# FPGA_Banks_DDR3.net
KiCad netlist of a schematic drawn in Altium Designer
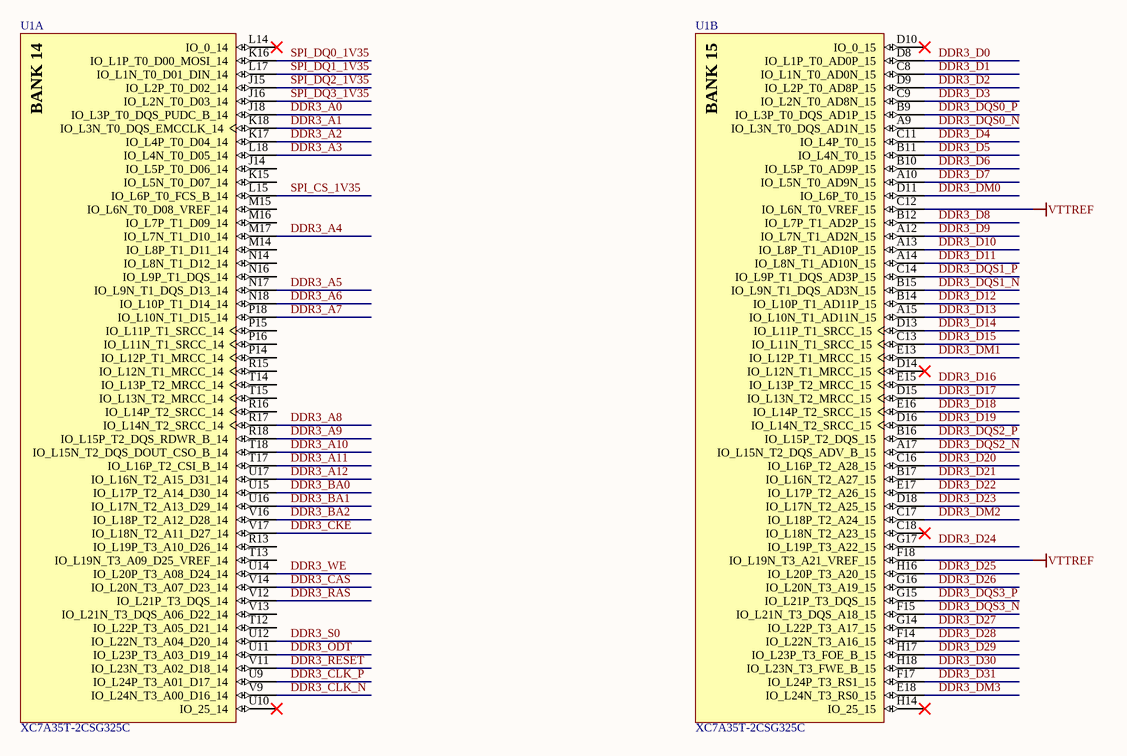
[diagram p0: FPGA_Banks_DDR3.SchDoc]

(export (version "E")
  (design (tool "Eeschema 10.0.6"))
  (components
    (comp (ref "U1")
      (value "XC7A35T-2CSG325C")
      (footprint "CSG325")
      (description "Artix-7 FPGA, 150 User I/Os, 4 GTP, 324-Ball BGA, Speed Grade 2, Commercial Grade, Pb-Free")
      (fields (field (name "MANUFACTURER") "Xilinx"))
      (libsource (lib "Xilinx Artix-7") (part "XC7A35T-2CSG325C"))
    )
  )
  (nets
    (net (code "1") (name "/DDR3_A0") (class "Default")
      (node (ref "U1") (pin "J18") (pinfunction "IO_L3P_T0_DQS_PUDC_B_14_J18") (pintype "bidirectional"))
    )
    (net (code "2") (name "/DDR3_A1") (class "Default")
      (node (ref "U1") (pin "K18") (pinfunction "IO_L3N_T0_DQS_EMCCLK_14_K18") (pintype "bidirectional"))
    )
    (net (code "3") (name "/DDR3_A2") (class "Default")
      (node (ref "U1") (pin "K17") (pinfunction "IO_L4P_T0_D04_14_K17") (pintype "bidirectional"))
    )
    (net (code "4") (name "/DDR3_A3") (class "Default")
      (node (ref "U1") (pin "L18") (pinfunction "IO_L4N_T0_D05_14_L18") (pintype "bidirectional"))
    )
    (net (code "5") (name "/DDR3_A4") (class "Default")
      (node (ref "U1") (pin "M17") (pinfunction "IO_L7N_T1_D10_14_M17") (pintype "bidirectional"))
    )
    (net (code "6") (name "/DDR3_A5") (class "Default")
      (node (ref "U1") (pin "N17") (pinfunction "IO_L9N_T1_DQS_D13_14_N17") (pintype "bidirectional"))
    )
    (net (code "7") (name "/DDR3_A6") (class "Default")
      (node (ref "U1") (pin "N18") (pinfunction "IO_L10P_T1_D14_14_N18") (pintype "bidirectional"))
    )
    (net (code "8") (name "/DDR3_A7") (class "Default")
      (node (ref "U1") (pin "P18") (pinfunction "IO_L10N_T1_D15_14_P18") (pintype "bidirectional"))
    )
    (net (code "9") (name "/DDR3_A8") (class "Default")
      (node (ref "U1") (pin "R17") (pinfunction "IO_L14N_T2_SRCC_14_R17") (pintype "bidirectional"))
    )
    (net (code "10") (name "/DDR3_A9") (class "Default")
      (node (ref "U1") (pin "R18") (pinfunction "IO_L15P_T2_DQS_RDWR_B_14_R18") (pintype "bidirectional"))
    )
    (net (code "11") (name "/DDR3_A10") (class "Default")
      (node (ref "U1") (pin "T18") (pinfunction "IO_L15N_T2_DQS_DOUT_CSO_B_14_T18") (pintype "bidirectional"))
    )
    (net (code "12") (name "/DDR3_A11") (class "Default")
      (node (ref "U1") (pin "T17") (pinfunction "IO_L16P_T2_CSI_B_14_T17") (pintype "bidirectional"))
    )
    (net (code "13") (name "/DDR3_A12") (class "Default")
      (node (ref "U1") (pin "U17") (pinfunction "IO_L16N_T2_A15_D31_14_U17") (pintype "bidirectional"))
    )
    (net (code "14") (name "/DDR3_BA0") (class "Default")
      (node (ref "U1") (pin "U15") (pinfunction "IO_L17P_T2_A14_D30_14_U15") (pintype "bidirectional"))
    )
    (net (code "15") (name "/DDR3_BA1") (class "Default")
      (node (ref "U1") (pin "U16") (pinfunction "IO_L17N_T2_A13_D29_14_U16") (pintype "bidirectional"))
    )
    (net (code "16") (name "/DDR3_BA2") (class "Default")
      (node (ref "U1") (pin "V16") (pinfunction "IO_L18P_T2_A12_D28_14_V16") (pintype "bidirectional"))
    )
    (net (code "17") (name "/DDR3_CAS") (class "Default")
      (node (ref "U1") (pin "V14") (pinfunction "IO_L20N_T3_A07_D23_14_V14") (pintype "bidirectional"))
    )
    (net (code "18") (name "/DDR3_CKE") (class "Default")
      (node (ref "U1") (pin "V17") (pinfunction "IO_L18N_T2_A11_D27_14_V17") (pintype "bidirectional"))
    )
    (net (code "19") (name "/DDR3_CLK_N") (class "Default")
      (node (ref "U1") (pin "V9") (pinfunction "IO_L24N_T3_A00_D16_14_V9") (pintype "bidirectional"))
    )
    (net (code "20") (name "/DDR3_CLK_P") (class "Default")
      (node (ref "U1") (pin "U9") (pinfunction "IO_L24P_T3_A01_D17_14_U9") (pintype "bidirectional"))
    )
    (net (code "21") (name "/DDR3_D0") (class "Default")
      (node (ref "U1") (pin "D8") (pinfunction "IO_L1P_T0_AD0P_15_D8") (pintype "bidirectional"))
    )
    (net (code "22") (name "/DDR3_D1") (class "Default")
      (node (ref "U1") (pin "C8") (pinfunction "IO_L1N_T0_AD0N_15_C8") (pintype "bidirectional"))
    )
    (net (code "23") (name "/DDR3_D2") (class "Default")
      (node (ref "U1") (pin "D9") (pinfunction "IO_L2P_T0_AD8P_15_D9") (pintype "bidirectional"))
    )
    (net (code "24") (name "/DDR3_D3") (class "Default")
      (node (ref "U1") (pin "C9") (pinfunction "IO_L2N_T0_AD8N_15_C9") (pintype "bidirectional"))
    )
    (net (code "25") (name "/DDR3_D4") (class "Default")
      (node (ref "U1") (pin "C11") (pinfunction "IO_L4P_T0_15_C11") (pintype "bidirectional"))
    )
    (net (code "26") (name "/DDR3_D5") (class "Default")
      (node (ref "U1") (pin "B11") (pinfunction "IO_L4N_T0_15_B11") (pintype "bidirectional"))
    )
    (net (code "27") (name "/DDR3_D6") (class "Default")
      (node (ref "U1") (pin "B10") (pinfunction "IO_L5P_T0_AD9P_15_B10") (pintype "bidirectional"))
    )
    (net (code "28") (name "/DDR3_D7") (class "Default")
      (node (ref "U1") (pin "A10") (pinfunction "IO_L5N_T0_AD9N_15_A10") (pintype "bidirectional"))
    )
    (net (code "29") (name "/DDR3_D8") (class "Default")
      (node (ref "U1") (pin "B12") (pinfunction "IO_L7P_T1_AD2P_15_B12") (pintype "bidirectional"))
    )
    (net (code "30") (name "/DDR3_D9") (class "Default")
      (node (ref "U1") (pin "A12") (pinfunction "IO_L7N_T1_AD2N_15_A12") (pintype "bidirectional"))
    )
    (net (code "31") (name "/DDR3_D10") (class "Default")
      (node (ref "U1") (pin "A13") (pinfunction "IO_L8P_T1_AD10P_15_A13") (pintype "bidirectional"))
    )
    (net (code "32") (name "/DDR3_D11") (class "Default")
      (node (ref "U1") (pin "A14") (pinfunction "IO_L8N_T1_AD10N_15_A14") (pintype "bidirectional"))
    )
    (net (code "33") (name "/DDR3_D12") (class "Default")
      (node (ref "U1") (pin "B14") (pinfunction "IO_L10P_T1_AD11P_15_B14") (pintype "bidirectional"))
    )
    (net (code "34") (name "/DDR3_D13") (class "Default")
      (node (ref "U1") (pin "A15") (pinfunction "IO_L10N_T1_AD11N_15_A15") (pintype "bidirectional"))
    )
    (net (code "35") (name "/DDR3_D14") (class "Default")
      (node (ref "U1") (pin "D13") (pinfunction "IO_L11P_T1_SRCC_15_D13") (pintype "bidirectional"))
    )
    (net (code "36") (name "/DDR3_D15") (class "Default")
      (node (ref "U1") (pin "C13") (pinfunction "IO_L11N_T1_SRCC_15_C13") (pintype "bidirectional"))
    )
    (net (code "37") (name "/DDR3_D16") (class "Default")
      (node (ref "U1") (pin "E15") (pinfunction "IO_L13P_T2_MRCC_15_E15") (pintype "bidirectional"))
    )
    (net (code "38") (name "/DDR3_D17") (class "Default")
      (node (ref "U1") (pin "D15") (pinfunction "IO_L13N_T2_MRCC_15_D15") (pintype "bidirectional"))
    )
    (net (code "39") (name "/DDR3_D18") (class "Default")
      (node (ref "U1") (pin "E16") (pinfunction "IO_L14P_T2_SRCC_15_E16") (pintype "bidirectional"))
    )
    (net (code "40") (name "/DDR3_D19") (class "Default")
      (node (ref "U1") (pin "D16") (pinfunction "IO_L14N_T2_SRCC_15_D16") (pintype "bidirectional"))
    )
    (net (code "41") (name "/DDR3_D20") (class "Default")
      (node (ref "U1") (pin "C16") (pinfunction "IO_L16P_T2_A28_15_C16") (pintype "bidirectional"))
    )
    (net (code "42") (name "/DDR3_D21") (class "Default")
      (node (ref "U1") (pin "B17") (pinfunction "IO_L16N_T2_A27_15_B17") (pintype "bidirectional"))
    )
    (net (code "43") (name "/DDR3_D22") (class "Default")
      (node (ref "U1") (pin "E17") (pinfunction "IO_L17P_T2_A26_15_E17") (pintype "bidirectional"))
    )
    (net (code "44") (name "/DDR3_D23") (class "Default")
      (node (ref "U1") (pin "D18") (pinfunction "IO_L17N_T2_A25_15_D18") (pintype "bidirectional"))
    )
    (net (code "45") (name "/DDR3_D24") (class "Default")
      (node (ref "U1") (pin "G17") (pinfunction "IO_L19P_T3_A22_15_G17") (pintype "bidirectional"))
    )
    (net (code "46") (name "/DDR3_D25") (class "Default")
      (node (ref "U1") (pin "H16") (pinfunction "IO_L20P_T3_A20_15_H16") (pintype "bidirectional"))
    )
    (net (code "47") (name "/DDR3_D26") (class "Default")
      (node (ref "U1") (pin "G16") (pinfunction "IO_L20N_T3_A19_15_G16") (pintype "bidirectional"))
    )
    (net (code "48") (name "/DDR3_D27") (class "Default")
      (node (ref "U1") (pin "G14") (pinfunction "IO_L22P_T3_A17_15_G14") (pintype "bidirectional"))
    )
    (net (code "49") (name "/DDR3_D28") (class "Default")
      (node (ref "U1") (pin "F14") (pinfunction "IO_L22N_T3_A16_15_F14") (pintype "bidirectional"))
    )
    (net (code "50") (name "/DDR3_D29") (class "Default")
      (node (ref "U1") (pin "H17") (pinfunction "IO_L23P_T3_FOE_B_15_H17") (pintype "bidirectional"))
    )
    (net (code "51") (name "/DDR3_D30") (class "Default")
      (node (ref "U1") (pin "H18") (pinfunction "IO_L23N_T3_FWE_B_15_H18") (pintype "bidirectional"))
    )
    (net (code "52") (name "/DDR3_D31") (class "Default")
      (node (ref "U1") (pin "F17") (pinfunction "IO_L24P_T3_RS1_15_F17") (pintype "bidirectional"))
    )
    (net (code "53") (name "/DDR3_DM0") (class "Default")
      (node (ref "U1") (pin "D11") (pinfunction "IO_L6P_T0_15_D11") (pintype "bidirectional"))
    )
    (net (code "54") (name "/DDR3_DM1") (class "Default")
      (node (ref "U1") (pin "E13") (pinfunction "IO_L12P_T1_MRCC_15_E13") (pintype "bidirectional"))
    )
    (net (code "55") (name "/DDR3_DM2") (class "Default")
      (node (ref "U1") (pin "C17") (pinfunction "IO_L18P_T2_A24_15_C17") (pintype "bidirectional"))
    )
    (net (code "56") (name "/DDR3_DM3") (class "Default")
      (node (ref "U1") (pin "E18") (pinfunction "IO_L24N_T3_RS0_15_E18") (pintype "bidirectional"))
    )
    (net (code "57") (name "/DDR3_DQS0_N") (class "Default")
      (node (ref "U1") (pin "A9") (pinfunction "IO_L3N_T0_DQS_AD1N_15_A9") (pintype "bidirectional"))
    )
    (net (code "58") (name "/DDR3_DQS0_P") (class "Default")
      (node (ref "U1") (pin "B9") (pinfunction "IO_L3P_T0_DQS_AD1P_15_B9") (pintype "bidirectional"))
    )
    (net (code "59") (name "/DDR3_DQS1_N") (class "Default")
      (node (ref "U1") (pin "B15") (pinfunction "IO_L9N_T1_DQS_AD3N_15_B15") (pintype "bidirectional"))
    )
    (net (code "60") (name "/DDR3_DQS1_P") (class "Default")
      (node (ref "U1") (pin "C14") (pinfunction "IO_L9P_T1_DQS_AD3P_15_C14") (pintype "bidirectional"))
    )
    (net (code "61") (name "/DDR3_DQS2_N") (class "Default")
      (node (ref "U1") (pin "A17") (pinfunction "IO_L15N_T2_DQS_ADV_B_15_A17") (pintype "bidirectional"))
    )
    (net (code "62") (name "/DDR3_DQS2_P") (class "Default")
      (node (ref "U1") (pin "B16") (pinfunction "IO_L15P_T2_DQS_15_B16") (pintype "bidirectional"))
    )
    (net (code "63") (name "/DDR3_DQS3_N") (class "Default")
      (node (ref "U1") (pin "F15") (pinfunction "IO_L21N_T3_DQS_A18_15_F15") (pintype "bidirectional"))
    )
    (net (code "64") (name "/DDR3_DQS3_P") (class "Default")
      (node (ref "U1") (pin "G15") (pinfunction "IO_L21P_T3_DQS_15_G15") (pintype "bidirectional"))
    )
    (net (code "65") (name "/DDR3_ODT") (class "Default")
      (node (ref "U1") (pin "U11") (pinfunction "IO_L23P_T3_A03_D19_14_U11") (pintype "bidirectional"))
    )
    (net (code "66") (name "/DDR3_RAS") (class "Default")
      (node (ref "U1") (pin "V12") (pinfunction "IO_L21P_T3_DQS_14_V12") (pintype "bidirectional"))
    )
    (net (code "67") (name "/DDR3_RESET") (class "Default")
      (node (ref "U1") (pin "V11") (pinfunction "IO_L23N_T3_A02_D18_14_V11") (pintype "bidirectional"))
    )
    (net (code "68") (name "/DDR3_S0") (class "Default")
      (node (ref "U1") (pin "U12") (pinfunction "IO_L22N_T3_A04_D20_14_U12") (pintype "bidirectional"))
    )
    (net (code "69") (name "/DDR3_WE") (class "Default")
      (node (ref "U1") (pin "U14") (pinfunction "IO_L20P_T3_A08_D24_14_U14") (pintype "bidirectional"))
    )
    (net (code "70") (name "/SPI_CS_1V35") (class "Default")
      (node (ref "U1") (pin "L15") (pinfunction "IO_L6P_T0_FCS_B_14_L15") (pintype "bidirectional"))
    )
    (net (code "71") (name "/SPI_DQ0_1V35") (class "Default")
      (node (ref "U1") (pin "K16") (pinfunction "IO_L1P_T0_D00_MOSI_14_K16") (pintype "bidirectional"))
    )
    (net (code "72") (name "/SPI_DQ1_1V35") (class "Default")
      (node (ref "U1") (pin "L17") (pinfunction "IO_L1N_T0_D01_DIN_14_L17") (pintype "bidirectional"))
    )
    (net (code "73") (name "/SPI_DQ2_1V35") (class "Default")
      (node (ref "U1") (pin "J15") (pinfunction "IO_L2P_T0_D02_14_J15") (pintype "bidirectional"))
    )
    (net (code "74") (name "/SPI_DQ3_1V35") (class "Default")
      (node (ref "U1") (pin "J16") (pinfunction "IO_L2N_T0_D03_14_J16") (pintype "bidirectional"))
    )
    (net (code "75") (name "VTTREF") (class "Default")
      (node (ref "U1") (pin "C12") (pinfunction "IO_L6N_T0_VREF_15_C12") (pintype "bidirectional"))
      (node (ref "U1") (pin "F18") (pinfunction "IO_L19N_T3_A21_VREF_15_F18") (pintype "bidirectional"))
    )
    (net (code "76") (name "unconnected-(U1A-IO_0_14-PadL14)") (class "Default")
      (node (ref "U1") (pin "L14") (pinfunction "IO_0_14_L14") (pintype "bidirectional+no_connect"))
    )
    (net (code "77") (name "unconnected-(U1A-IO_25_14-PadU10)") (class "Default")
      (node (ref "U1") (pin "U10") (pinfunction "IO_25_14_U10") (pintype "bidirectional+no_connect"))
    )
    (net (code "78") (name "unconnected-(U1A-IO_L5N_T0_D07_14-PadK15)") (class "Default")
      (node (ref "U1") (pin "K15") (pinfunction "IO_L5N_T0_D07_14_K15") (pintype "bidirectional"))
    )
    (net (code "79") (name "unconnected-(U1A-IO_L5P_T0_D06_14-PadJ14)") (class "Default")
      (node (ref "U1") (pin "J14") (pinfunction "IO_L5P_T0_D06_14_J14") (pintype "bidirectional"))
    )
    (net (code "80") (name "unconnected-(U1A-IO_L6N_T0_D08_VREF_14-PadM15)") (class "Default")
      (node (ref "U1") (pin "M15") (pinfunction "IO_L6N_T0_D08_VREF_14_M15") (pintype "bidirectional"))
    )
    (net (code "81") (name "unconnected-(U1A-IO_L7P_T1_D09_14-PadM16)") (class "Default")
      (node (ref "U1") (pin "M16") (pinfunction "IO_L7P_T1_D09_14_M16") (pintype "bidirectional"))
    )
    (net (code "82") (name "unconnected-(U1A-IO_L8N_T1_D12_14-PadN14)") (class "Default")
      (node (ref "U1") (pin "N14") (pinfunction "IO_L8N_T1_D12_14_N14") (pintype "bidirectional"))
    )
    (net (code "83") (name "unconnected-(U1A-IO_L8P_T1_D11_14-PadM14)") (class "Default")
      (node (ref "U1") (pin "M14") (pinfunction "IO_L8P_T1_D11_14_M14") (pintype "bidirectional"))
    )
    (net (code "84") (name "unconnected-(U1A-IO_L9P_T1_DQS_14-PadN16)") (class "Default")
      (node (ref "U1") (pin "N16") (pinfunction "IO_L9P_T1_DQS_14_N16") (pintype "bidirectional"))
    )
    (net (code "85") (name "unconnected-(U1A-IO_L11N_T1_SRCC_14-PadP16)") (class "Default")
      (node (ref "U1") (pin "P16") (pinfunction "IO_L11N_T1_SRCC_14_P16") (pintype "bidirectional"))
    )
    (net (code "86") (name "unconnected-(U1A-IO_L11P_T1_SRCC_14-PadP15)") (class "Default")
      (node (ref "U1") (pin "P15") (pinfunction "IO_L11P_T1_SRCC_14_P15") (pintype "bidirectional"))
    )
    (net (code "87") (name "unconnected-(U1A-IO_L12N_T1_MRCC_14-PadR15)") (class "Default")
      (node (ref "U1") (pin "R15") (pinfunction "IO_L12N_T1_MRCC_14_R15") (pintype "bidirectional"))
    )
    (net (code "88") (name "unconnected-(U1A-IO_L12P_T1_MRCC_14-PadP14)") (class "Default")
      (node (ref "U1") (pin "P14") (pinfunction "IO_L12P_T1_MRCC_14_P14") (pintype "bidirectional"))
    )
    (net (code "89") (name "unconnected-(U1A-IO_L13N_T2_MRCC_14-PadT15)") (class "Default")
      (node (ref "U1") (pin "T15") (pinfunction "IO_L13N_T2_MRCC_14_T15") (pintype "bidirectional"))
    )
    (net (code "90") (name "unconnected-(U1A-IO_L13P_T2_MRCC_14-PadT14)") (class "Default")
      (node (ref "U1") (pin "T14") (pinfunction "IO_L13P_T2_MRCC_14_T14") (pintype "bidirectional"))
    )
    (net (code "91") (name "unconnected-(U1A-IO_L14P_T2_SRCC_14-PadR16)") (class "Default")
      (node (ref "U1") (pin "R16") (pinfunction "IO_L14P_T2_SRCC_14_R16") (pintype "bidirectional"))
    )
    (net (code "92") (name "unconnected-(U1A-IO_L19N_T3_A09_D25_VREF_14-PadT13)") (class "Default")
      (node (ref "U1") (pin "T13") (pinfunction "IO_L19N_T3_A09_D25_VREF_14_T13") (pintype "bidirectional"))
    )
    (net (code "93") (name "unconnected-(U1A-IO_L19P_T3_A10_D26_14-PadR13)") (class "Default")
      (node (ref "U1") (pin "R13") (pinfunction "IO_L19P_T3_A10_D26_14_R13") (pintype "bidirectional"))
    )
    (net (code "94") (name "unconnected-(U1A-IO_L21N_T3_DQS_A06_D22_14-PadV13)") (class "Default")
      (node (ref "U1") (pin "V13") (pinfunction "IO_L21N_T3_DQS_A06_D22_14_V13") (pintype "bidirectional"))
    )
    (net (code "95") (name "unconnected-(U1A-IO_L22P_T3_A05_D21_14-PadT12)") (class "Default")
      (node (ref "U1") (pin "T12") (pinfunction "IO_L22P_T3_A05_D21_14_T12") (pintype "bidirectional"))
    )
    (net (code "96") (name "unconnected-(U1B-IO_0_15-PadD10)") (class "Default")
      (node (ref "U1") (pin "D10") (pinfunction "IO_0_15_D10") (pintype "bidirectional+no_connect"))
    )
    (net (code "97") (name "unconnected-(U1B-IO_25_15-PadH14)") (class "Default")
      (node (ref "U1") (pin "H14") (pinfunction "IO_25_15_H14") (pintype "bidirectional+no_connect"))
    )
    (net (code "98") (name "unconnected-(U1B-IO_L12N_T1_MRCC_15-PadD14)") (class "Default")
      (node (ref "U1") (pin "D14") (pinfunction "IO_L12N_T1_MRCC_15_D14") (pintype "bidirectional+no_connect"))
    )
    (net (code "99") (name "unconnected-(U1B-IO_L18N_T2_A23_15-PadC18)") (class "Default")
      (node (ref "U1") (pin "C18") (pinfunction "IO_L18N_T2_A23_15_C18") (pintype "bidirectional+no_connect"))
    )
  )
)
